# USB_Multiplicator_2025.net
KiCad netlist of a schematic drawn in EAGLE
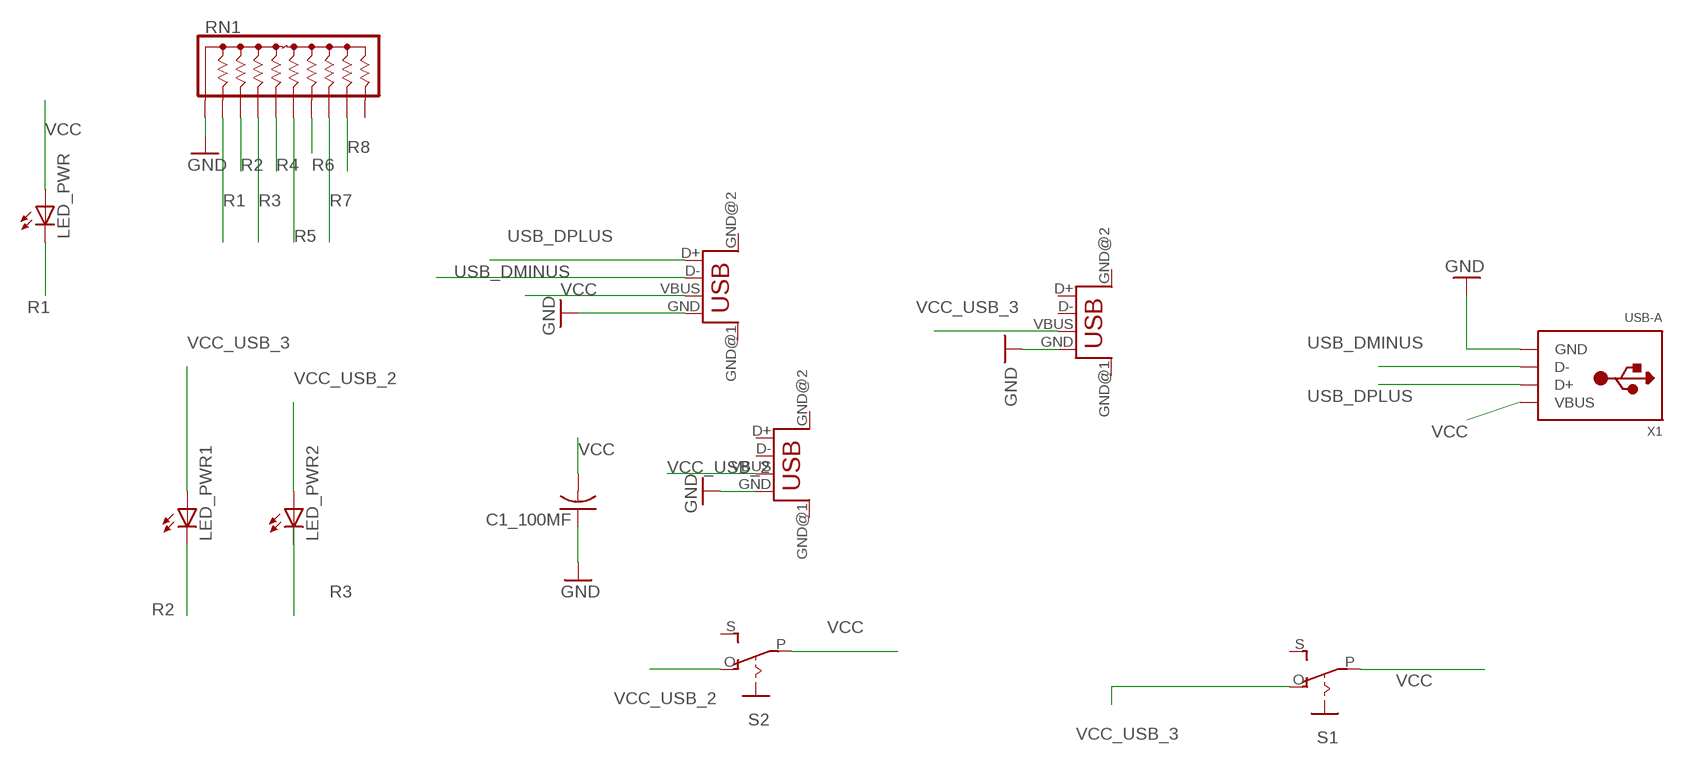
[diagram p0: schematic, sheet 1]

(export (version "E")
  (design (tool "Eeschema 10.0.6"))
  (components
    (comp (ref "C1_100MF")
      (value "C-US025-030X050")
      (footprint "eagle-import:C025-030X050")
      (libsource (lib "eagle-import") (part "C-US025-030X050"))
    )
    (comp (ref "LED_PWR")
      (value "LEDSMT1206")
      (footprint "eagle-import:1206")
      (libsource (lib "eagle-import") (part "LEDSMT1206"))
    )
    (comp (ref "LED_PWR1")
      (value "LEDSMT1206")
      (footprint "eagle-import:1206")
      (libsource (lib "eagle-import") (part "LEDSMT1206"))
    )
    (comp (ref "LED_PWR2")
      (value "LEDSMT1206")
      (footprint "eagle-import:1206")
      (libsource (lib "eagle-import") (part "LEDSMT1206"))
    )
    (comp (ref "RN1")
      (value "4610X")
      (footprint "eagle-import:SIP10")
      (libsource (lib "eagle-import") (part "4610X"))
    )
    (comp (ref "S1")
      (value "EG1218S")
      (footprint "eagle-import:EG1218")
      (libsource (lib "eagle-import") (part "EG1218S"))
    )
    (comp (ref "S2")
      (value "EG1218S")
      (footprint "eagle-import:EG1218")
      (libsource (lib "eagle-import") (part "EG1218S"))
    )
    (comp (ref "USB_OUT_1")
      (value "USB")
      (footprint "eagle-import:USB-FEMALE-A-PTH")
      (libsource (lib "eagle-import") (part "USB"))
    )
    (comp (ref "USB_OUT_2")
      (value "USB")
      (footprint "eagle-import:USB-FEMALE-A-PTH")
      (libsource (lib "eagle-import") (part "USB"))
    )
    (comp (ref "USB_OUT_WITH_DATA_1")
      (value "USB")
      (footprint "eagle-import:USB-FEMALE-A-PTH")
      (libsource (lib "eagle-import") (part "USB"))
    )
    (comp (ref "X1")
      (value "USB-A")
      (footprint "eagle-import:MOLEX_480371000")
      (libsource (lib "eagle-import") (part "USB-A"))
    )
  )
  (nets
    (net (code "1") (name "/R1") (class "Default")
      (node (ref "LED_PWR") (pin "C") (pinfunction "C_C") (pintype "passive"))
      (node (ref "RN1") (pin "2") (pinfunction "2_2") (pintype "passive"))
    )
    (net (code "2") (name "/R2") (class "Default")
      (node (ref "LED_PWR1") (pin "C") (pinfunction "C_C") (pintype "passive"))
      (node (ref "RN1") (pin "3") (pinfunction "3_3") (pintype "passive"))
    )
    (net (code "3") (name "/R3") (class "Default")
      (node (ref "LED_PWR2") (pin "C") (pinfunction "C_C") (pintype "passive"))
      (node (ref "RN1") (pin "4") (pinfunction "4_4") (pintype "passive"))
    )
    (net (code "4") (name "/R4") (class "Default")
      (node (ref "RN1") (pin "5") (pinfunction "5_5") (pintype "passive"))
    )
    (net (code "5") (name "/R5") (class "Default")
      (node (ref "RN1") (pin "6") (pinfunction "6_6") (pintype "passive"))
    )
    (net (code "6") (name "/R6") (class "Default")
      (node (ref "RN1") (pin "7") (pinfunction "7_7") (pintype "passive"))
    )
    (net (code "7") (name "/R7") (class "Default")
      (node (ref "RN1") (pin "8") (pinfunction "8_8") (pintype "passive"))
    )
    (net (code "8") (name "/R8") (class "Default")
      (node (ref "RN1") (pin "9") (pinfunction "9_9") (pintype "passive"))
    )
    (net (code "9") (name "/USB_DMINUS") (class "Default")
      (node (ref "USB_OUT_WITH_DATA_1") (pin "D-") (pinfunction "D-_D-") (pintype "bidirectional"))
      (node (ref "X1") (pin "2") (pinfunction "D-_2") (pintype "bidirectional"))
    )
    (net (code "10") (name "/USB_DPLUS") (class "Default")
      (node (ref "USB_OUT_WITH_DATA_1") (pin "D+") (pinfunction "D+_D+") (pintype "bidirectional"))
      (node (ref "X1") (pin "3") (pinfunction "D+_3") (pintype "bidirectional"))
    )
    (net (code "11") (name "/VCC") (class "Default")
      (node (ref "C1_100MF") (pin "2") (pinfunction "2_2") (pintype "passive"))
      (node (ref "LED_PWR") (pin "A") (pinfunction "A_A") (pintype "passive"))
      (node (ref "S1") (pin "P") (pinfunction "P_P") (pintype "passive"))
      (node (ref "S2") (pin "P") (pinfunction "P_P") (pintype "passive"))
      (node (ref "USB_OUT_WITH_DATA_1") (pin "VBUS") (pinfunction "VBUS_VBUS") (pintype "bidirectional"))
      (node (ref "X1") (pin "1") (pinfunction "VBUS_1") (pintype "power_in"))
    )
    (net (code "12") (name "/VCC_USB_2") (class "Default")
      (node (ref "LED_PWR2") (pin "A") (pinfunction "A_A") (pintype "passive"))
      (node (ref "S2") (pin "O") (pinfunction "O_O") (pintype "passive"))
      (node (ref "USB_OUT_2") (pin "VBUS") (pinfunction "VBUS_VBUS") (pintype "bidirectional"))
    )
    (net (code "13") (name "/VCC_USB_3") (class "Default")
      (node (ref "LED_PWR1") (pin "A") (pinfunction "A_A") (pintype "passive"))
      (node (ref "S1") (pin "O") (pinfunction "O_O") (pintype "passive"))
      (node (ref "USB_OUT_1") (pin "VBUS") (pinfunction "VBUS_VBUS") (pintype "bidirectional"))
    )
    (net (code "14") (name "GND") (class "Default")
      (node (ref "C1_100MF") (pin "1") (pinfunction "1_1") (pintype "passive"))
      (node (ref "RN1") (pin "1") (pinfunction "1_1") (pintype "passive"))
      (node (ref "USB_OUT_1") (pin "GND") (pinfunction "GND_GND") (pintype "bidirectional"))
      (node (ref "USB_OUT_2") (pin "GND") (pinfunction "GND_GND") (pintype "bidirectional"))
      (node (ref "USB_OUT_WITH_DATA_1") (pin "GND") (pinfunction "GND_GND") (pintype "bidirectional"))
      (node (ref "X1") (pin "4") (pinfunction "GND_4") (pintype "power_in"))
    )
    (net (code "15") (name "unconnected-(RN1-Pad10)") (class "Default")
      (node (ref "RN1") (pin "10") (pinfunction "10_10") (pintype "passive"))
    )
    (net (code "16") (name "unconnected-(S1-PadS)") (class "Default")
      (node (ref "S1") (pin "S") (pinfunction "S_S") (pintype "passive"))
    )
    (net (code "17") (name "unconnected-(S2-PadS)") (class "Default")
      (node (ref "S2") (pin "S") (pinfunction "S_S") (pintype "passive"))
    )
    (net (code "18") (name "unconnected-(USB_OUT_1-GND-PadGND@1)") (class "Default")
      (node (ref "USB_OUT_1") (pin "GND@1") (pinfunction "GND_GND@1") (pintype "bidirectional"))
    )
    (net (code "19") (name "unconnected-(USB_OUT_1-GND-PadGND@2)") (class "Default")
      (node (ref "USB_OUT_1") (pin "GND@2") (pinfunction "GND_GND@2") (pintype "bidirectional"))
    )
    (net (code "20") (name "unconnected-(USB_OUT_1-PadD+)") (class "Default")
      (node (ref "USB_OUT_1") (pin "D+") (pinfunction "D+_D+") (pintype "bidirectional"))
    )
    (net (code "21") (name "unconnected-(USB_OUT_1-PadD-)") (class "Default")
      (node (ref "USB_OUT_1") (pin "D-") (pinfunction "D-_D-") (pintype "bidirectional"))
    )
    (net (code "22") (name "unconnected-(USB_OUT_2-GND-PadGND@1)") (class "Default")
      (node (ref "USB_OUT_2") (pin "GND@1") (pinfunction "GND_GND@1") (pintype "bidirectional"))
    )
    (net (code "23") (name "unconnected-(USB_OUT_2-GND-PadGND@2)") (class "Default")
      (node (ref "USB_OUT_2") (pin "GND@2") (pinfunction "GND_GND@2") (pintype "bidirectional"))
    )
    (net (code "24") (name "unconnected-(USB_OUT_2-PadD+)") (class "Default")
      (node (ref "USB_OUT_2") (pin "D+") (pinfunction "D+_D+") (pintype "bidirectional"))
    )
    (net (code "25") (name "unconnected-(USB_OUT_2-PadD-)") (class "Default")
      (node (ref "USB_OUT_2") (pin "D-") (pinfunction "D-_D-") (pintype "bidirectional"))
    )
    (net (code "26") (name "unconnected-(USB_OUT_WITH_DATA_1-GND-PadGND@1)") (class "Default")
      (node (ref "USB_OUT_WITH_DATA_1") (pin "GND@1") (pinfunction "GND_GND@1") (pintype "bidirectional"))
    )
    (net (code "27") (name "unconnected-(USB_OUT_WITH_DATA_1-GND-PadGND@2)") (class "Default")
      (node (ref "USB_OUT_WITH_DATA_1") (pin "GND@2") (pinfunction "GND_GND@2") (pintype "bidirectional"))
    )
  )
)
